# PX4FLOW1_3_1.net
KiCad netlist of a schematic drawn in EAGLE
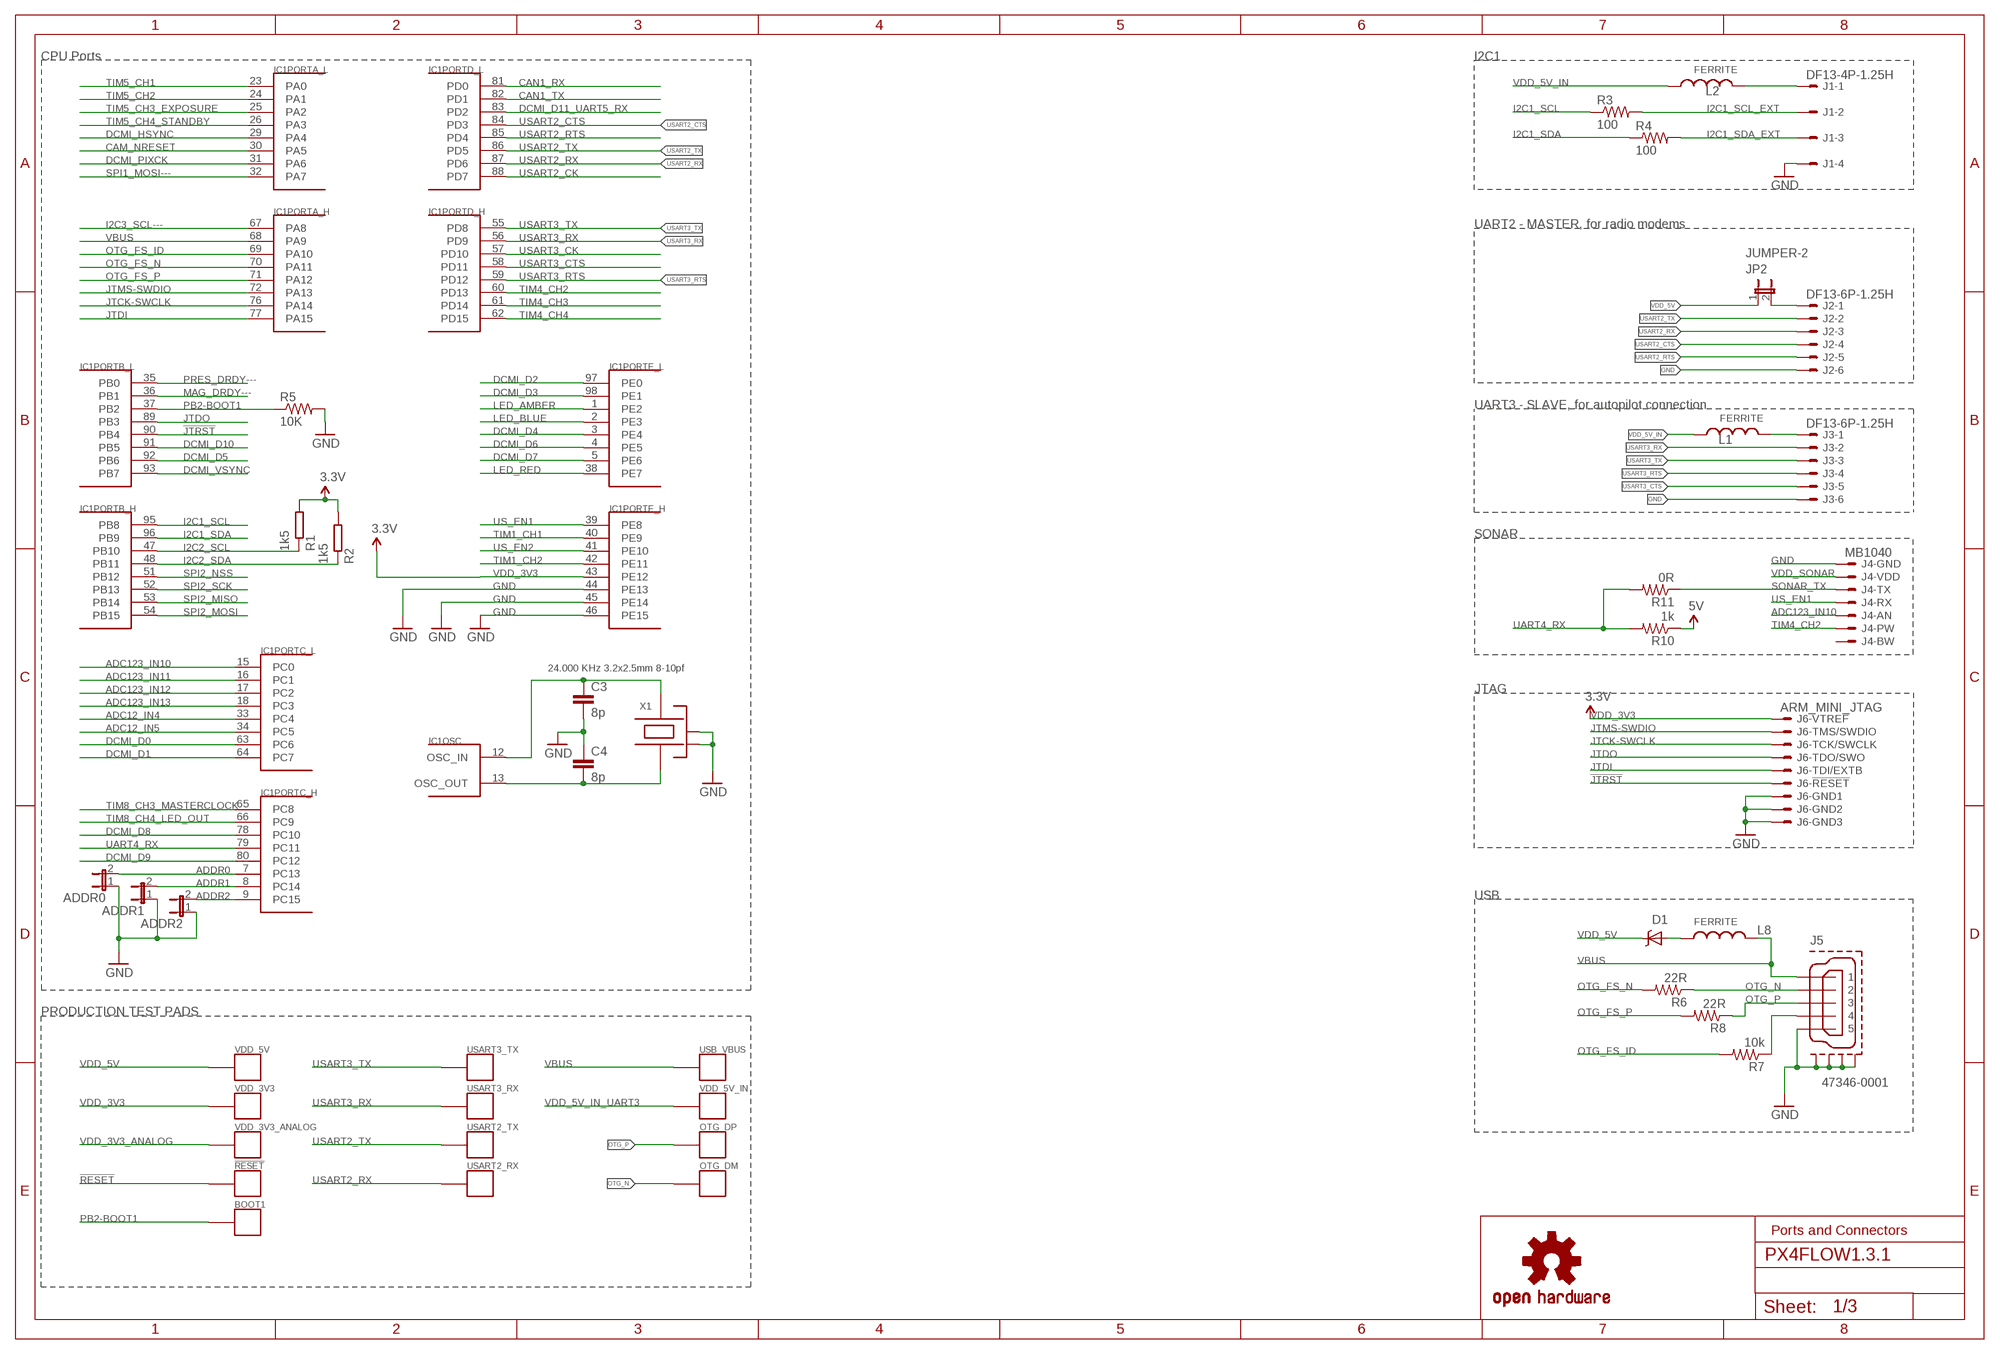
[diagram p0: schematic, sheet 1]
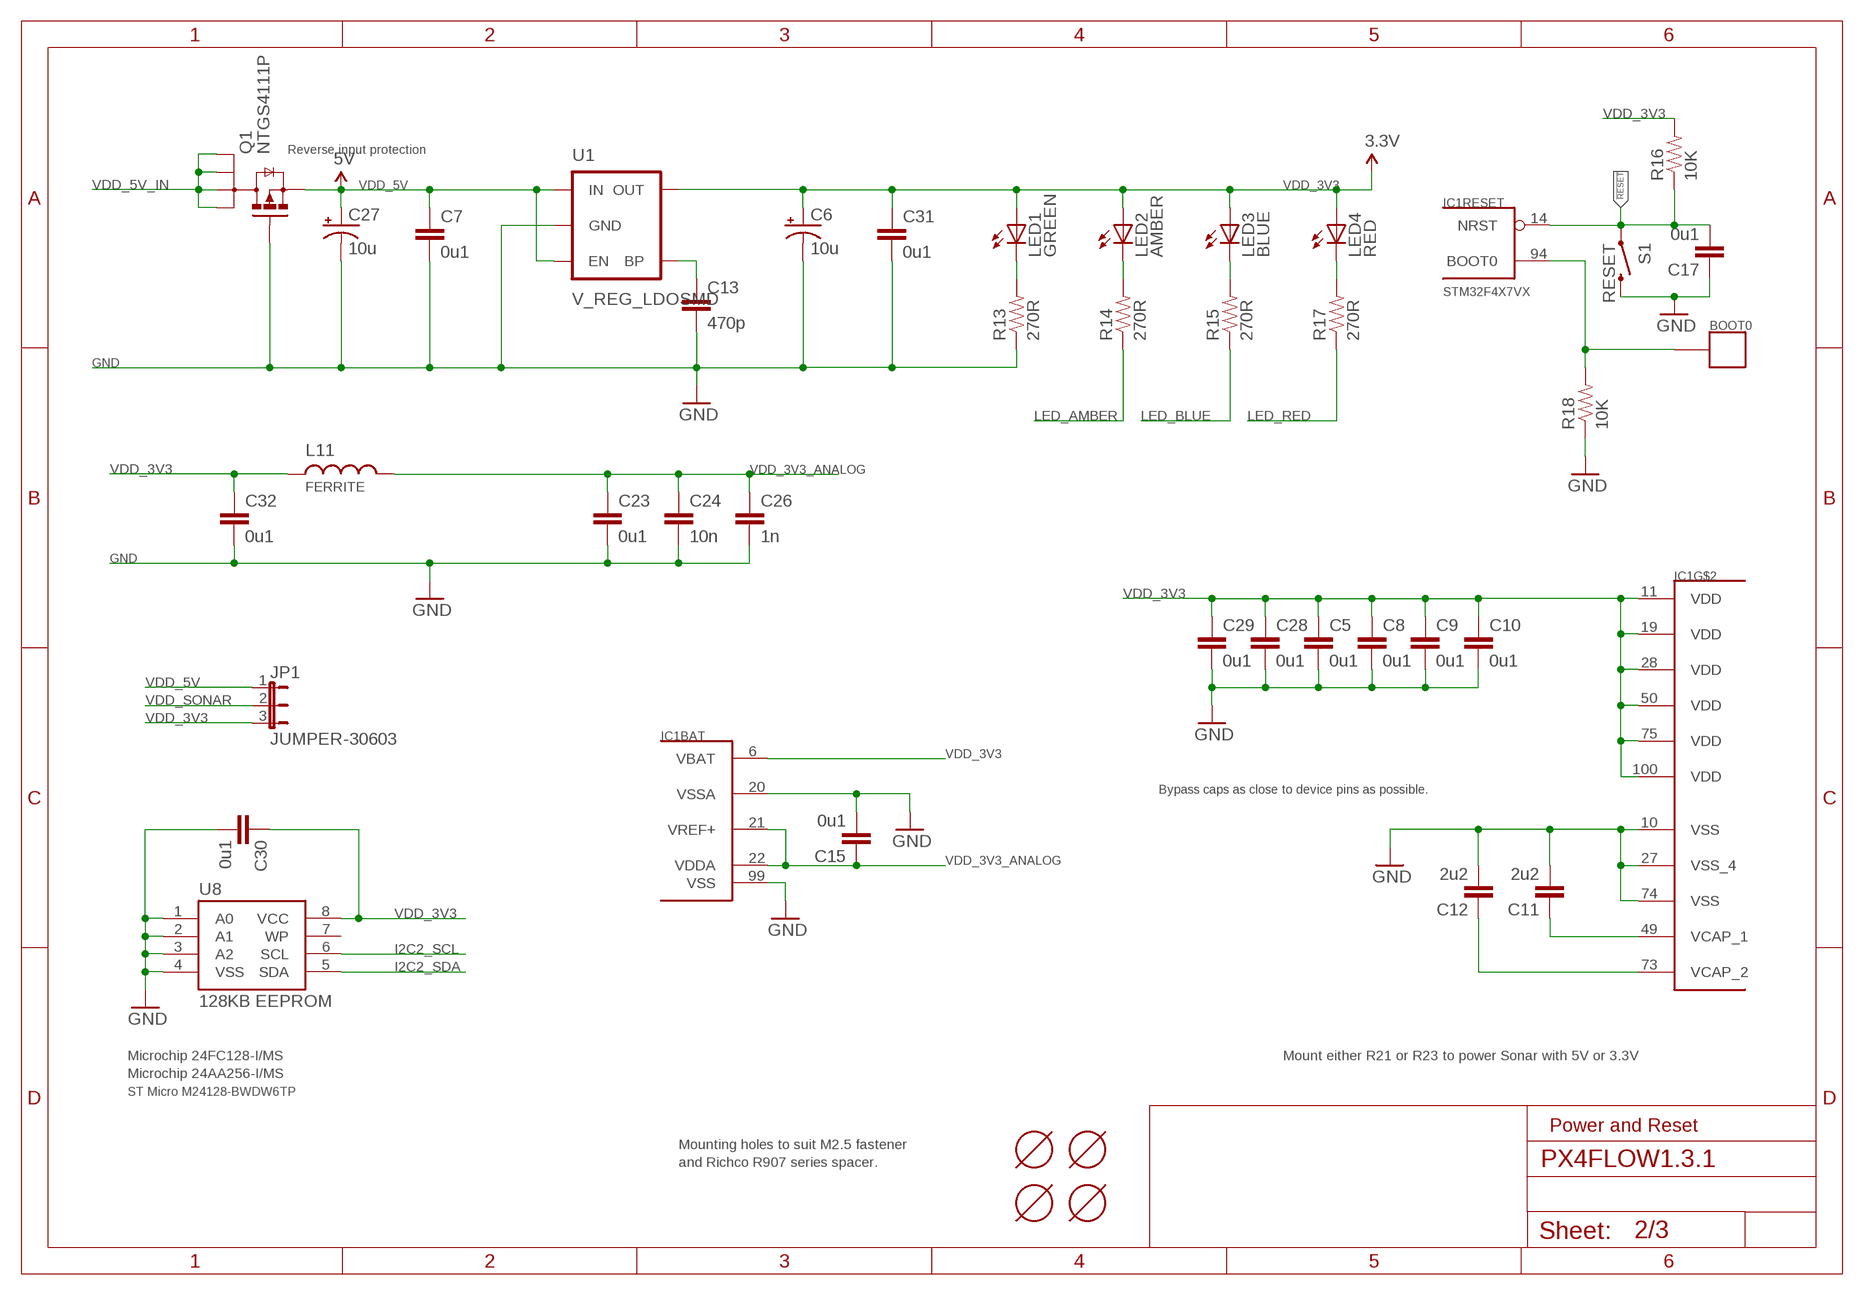
[diagram p1: schematic, sheet 2]
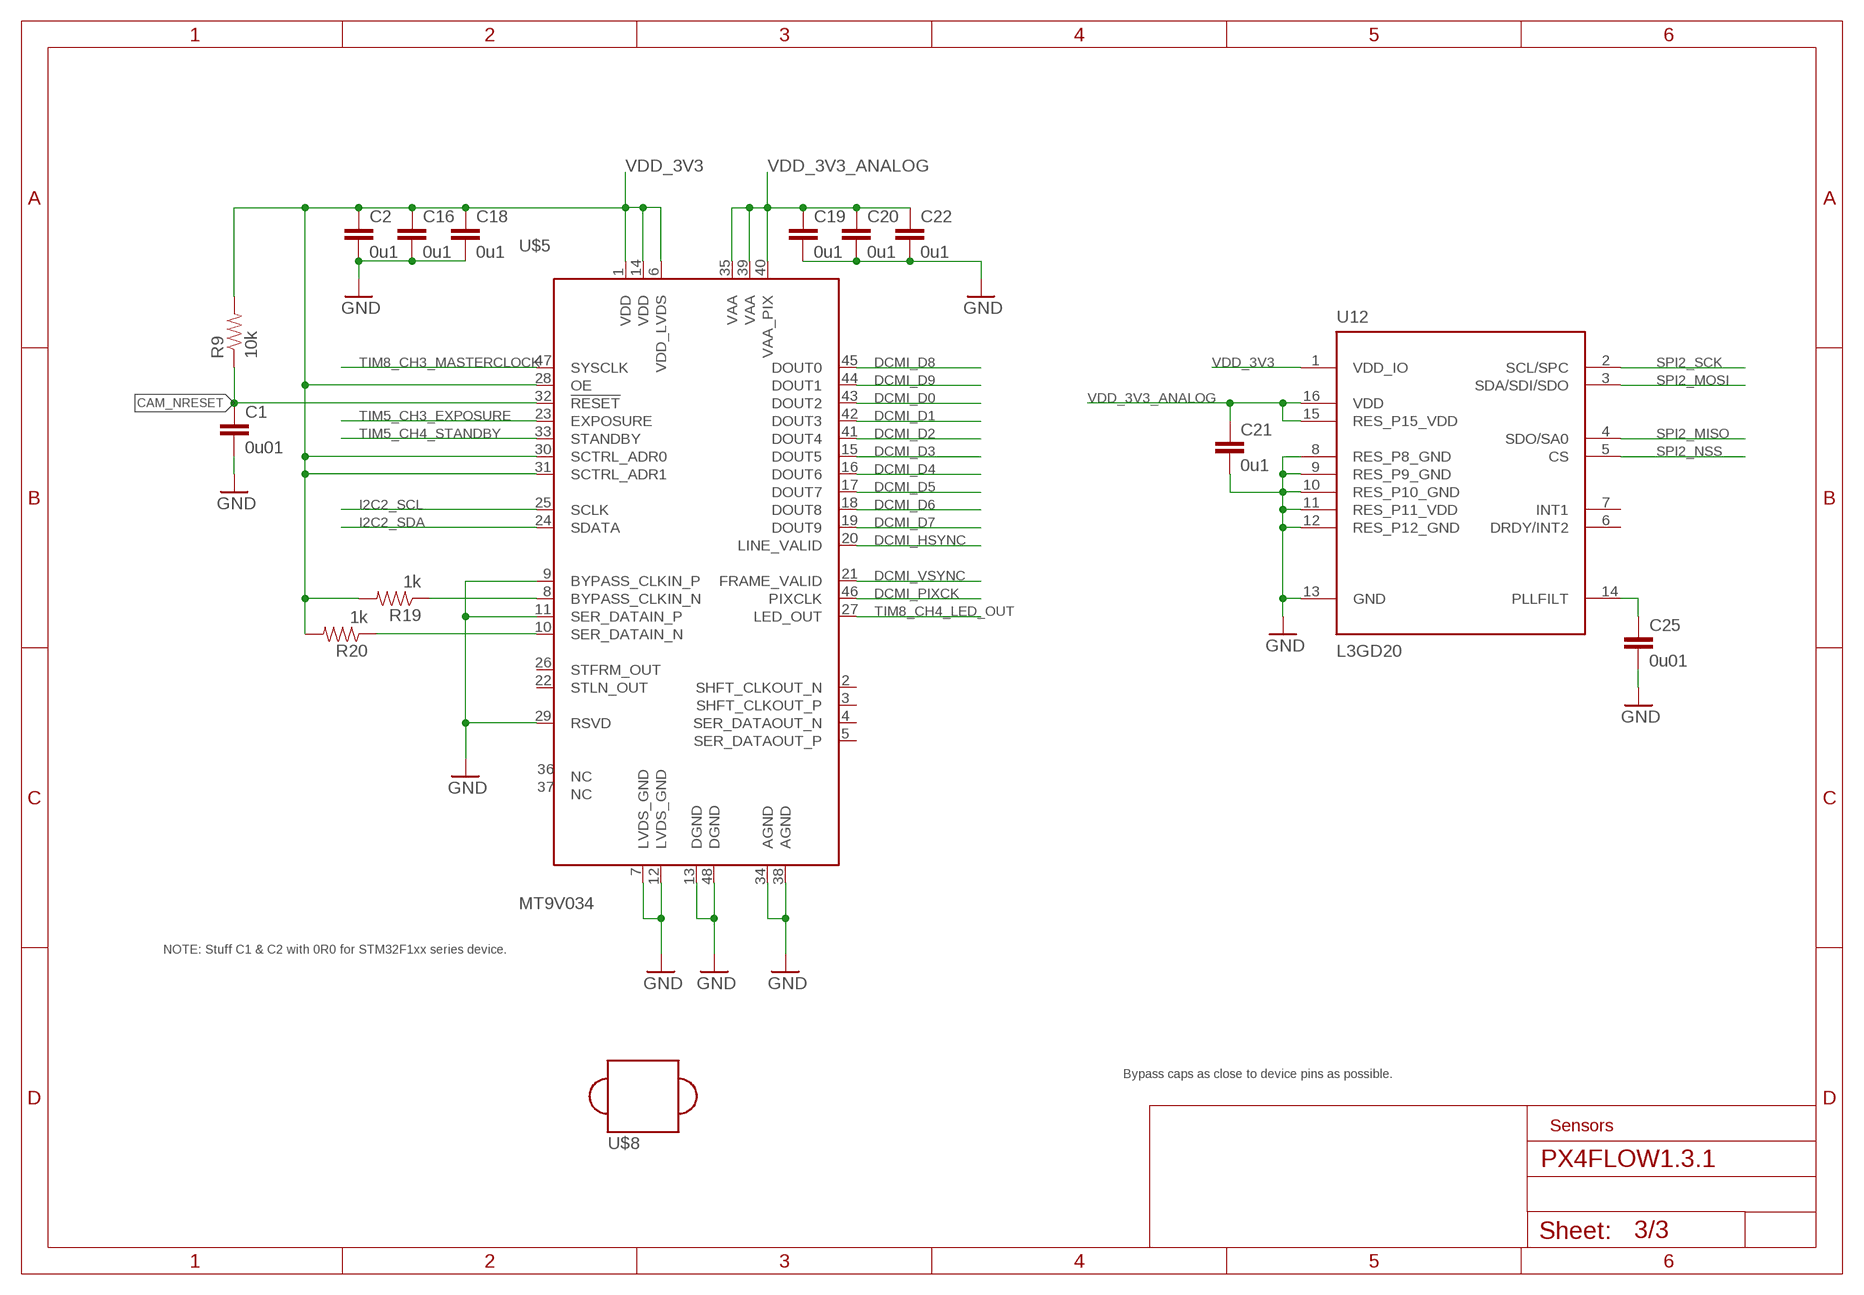
[diagram p2: schematic, sheet 3]

(export (version "E")
  (design (tool "Eeschema 10.0.6"))
  (components
    (comp (ref "BOOT0")
      (value "PAD.05")
      (footprint "eagle-import:PAD.05X.05")
      (libsource (lib "eagle-import") (part "PAD.05"))
    )
    (comp (ref "C5")
      (value "0u1")
      (footprint "eagle-import:0402-CAP")
      (fields (field (name "PARTNO") "CC0402ZRY5V7BB104"))
      (libsource (lib "eagle-import") (part "CAP0402-CAP"))
    )
    (comp (ref "C6")
      (value "10u")
      (footprint "eagle-import:EIA3216")
      (fields (field (name "PARTNO") "F931A106MAA"))
      (libsource (lib "eagle-import") (part "CAP_POL1206"))
    )
    (comp (ref "C7")
      (value "0u1")
      (footprint "eagle-import:0402-CAP")
      (fields (field (name "PARTNO") "CC0402ZRY5V7BB104"))
      (libsource (lib "eagle-import") (part "CAP0402-CAP"))
    )
    (comp (ref "C8")
      (value "0u1")
      (footprint "eagle-import:0402-CAP")
      (fields (field (name "PARTNO") "CC0402ZRY5V7BB104"))
      (libsource (lib "eagle-import") (part "CAP0402-CAP"))
    )
    (comp (ref "C9")
      (value "0u1")
      (footprint "eagle-import:0402-CAP")
      (fields (field (name "PARTNO") "CC0402ZRY5V7BB104"))
      (libsource (lib "eagle-import") (part "CAP0402-CAP"))
    )
    (comp (ref "C10")
      (value "0u1")
      (footprint "eagle-import:0402-CAP")
      (fields (field (name "PARTNO") "CC0402ZRY5V7BB104"))
      (libsource (lib "eagle-import") (part "CAP0402-CAP"))
    )
    (comp (ref "C11")
      (value "2u2")
      (footprint "eagle-import:0402-CAP")
      (fields (field (name "PARTNO") "C1608Y5V1C225Z"))
      (libsource (lib "eagle-import") (part "CAP0402-CAP"))
    )
    (comp (ref "C12")
      (value "2u2")
      (footprint "eagle-import:0402-CAP")
      (fields (field (name "PARTNO") "C1608Y5V1C225Z"))
      (libsource (lib "eagle-import") (part "CAP0402-CAP"))
    )
    (comp (ref "C13")
      (value "470p")
      (footprint "eagle-import:0402-CAP")
      (fields (field (name "PARTNO") "CC0402KRX7R9BB471"))
      (libsource (lib "eagle-import") (part "CAP0402-CAP"))
    )
    (comp (ref "C15")
      (value "0u1")
      (footprint "eagle-import:0402-CAP")
      (fields (field (name "PARTNO") "CC0402ZRY5V7BB104"))
      (libsource (lib "eagle-import") (part "CAP0402-CAP"))
    )
    (comp (ref "C17")
      (value "0u1")
      (footprint "eagle-import:0402-CAP")
      (fields (field (name "PARTNO") "CC0402ZRY5V7BB104"))
      (libsource (lib "eagle-import") (part "CAP0402-CAP"))
    )
    (comp (ref "C23")
      (value "0u1")
      (footprint "eagle-import:0402-CAP")
      (fields (field (name "PARTNO") "CC0402ZRY5V7BB104"))
      (libsource (lib "eagle-import") (part "CAP0402-CAP"))
    )
    (comp (ref "C24")
      (value "10n")
      (footprint "eagle-import:0402-CAP")
      (fields (field (name "PARTNO") "CC0402ZRY5V7BB104"))
      (libsource (lib "eagle-import") (part "CAP0402-CAP"))
    )
    (comp (ref "C26")
      (value "1n")
      (footprint "eagle-import:0402-CAP")
      (fields (field (name "PARTNO") "CC0402ZRY5V7BB104"))
      (libsource (lib "eagle-import") (part "CAP0402-CAP"))
    )
    (comp (ref "C27")
      (value "10u")
      (footprint "eagle-import:EIA3216")
      (fields (field (name "PARTNO") "F931A106MAA"))
      (libsource (lib "eagle-import") (part "CAP_POL1206"))
    )
    (comp (ref "C28")
      (value "0u1")
      (footprint "eagle-import:0402-CAP")
      (fields (field (name "PARTNO") "CC0402ZRY5V7BB104"))
      (libsource (lib "eagle-import") (part "CAP0402-CAP"))
    )
    (comp (ref "C29")
      (value "0u1")
      (footprint "eagle-import:0402-CAP")
      (fields (field (name "PARTNO") "CC0402ZRY5V7BB104"))
      (libsource (lib "eagle-import") (part "CAP0402-CAP"))
    )
    (comp (ref "C30")
      (value "0u1")
      (footprint "eagle-import:0402-CAP")
      (fields (field (name "PARTNO") "CC0402ZRY5V7BB104"))
      (libsource (lib "eagle-import") (part "CAP0402-CAP"))
    )
    (comp (ref "C31")
      (value "0u1")
      (footprint "eagle-import:0402-CAP")
      (fields (field (name "PARTNO") "CC0402ZRY5V7BB104"))
      (libsource (lib "eagle-import") (part "CAP0402-CAP"))
    )
    (comp (ref "C32")
      (value "0u1")
      (footprint "eagle-import:0402-CAP")
      (fields (field (name "PARTNO") "CC0402ZRY5V7BB104"))
      (libsource (lib "eagle-import") (part "CAP0402-CAP"))
    )
    (comp (ref "IC1")
      (value "STM32F4X7VX")
      (footprint "eagle-import:TQFP100")
      (fields (field (name "PARTNO") "STM32F407VGT6"))
      (libsource (lib "eagle-import") (part "STM32F4X7VX"))
    )
    (comp (ref "JP1")
      (value "JUMPER-30603")
      (footprint "eagle-import:SJ_3_0603_PASTE1&2")
      (fields (field (name "PARTNO") "RMCF0402ZT0R00"))
      (libsource (lib "eagle-import") (part "JUMPER-30603"))
    )
    (comp (ref "L11")
      (value "FERRITE")
      (footprint "eagle-import:0402-IND")
      (fields (field (name "PARTNO") "BKP1005HS121-T"))
      (libsource (lib "eagle-import") (part "INDUCTOR0402"))
    )
    (comp (ref "LED1")
      (value "GREEN")
      (footprint "eagle-import:LED-0603")
      (fields (field (name "PARTNO") "LNJ337W83RA"))
      (libsource (lib "eagle-import") (part "LED0603"))
    )
    (comp (ref "LED2")
      (value "AMBER")
      (footprint "eagle-import:LED-0603")
      (fields (field (name "PARTNO") "LNJ437W84RA"))
      (libsource (lib "eagle-import") (part "LED0603"))
    )
    (comp (ref "LED3")
      (value "BLUE")
      (footprint "eagle-import:LED-0603")
      (fields (field (name "PARTNO") "LNJ937W8CRA"))
      (libsource (lib "eagle-import") (part "LED0603"))
    )
    (comp (ref "LED4")
      (value "RED")
      (footprint "eagle-import:LED-0603")
      (fields (field (name "PARTNO") "LNJ237W82RA"))
      (libsource (lib "eagle-import") (part "LED0603"))
    )
    (comp (ref "Q1")
      (value "NTGS4111P")
      (footprint "eagle-import:TSOP-6")
      (libsource (lib "eagle-import") (part "NTGS4111P"))
    )
    (comp (ref "R13")
      (value "270R")
      (footprint "eagle-import:0402-RES")
      (fields (field (name "PARTNO") "MCR01MZPJ271"))
      (libsource (lib "eagle-import") (part "RESISTOR0402-RES"))
    )
    (comp (ref "R14")
      (value "270R")
      (footprint "eagle-import:0402-RES")
      (fields (field (name "PARTNO") "MCR01MZPJ271"))
      (libsource (lib "eagle-import") (part "RESISTOR0402-RES"))
    )
    (comp (ref "R15")
      (value "270R")
      (footprint "eagle-import:0402-RES")
      (fields (field (name "PARTNO") "MCR01MZPJ820"))
      (libsource (lib "eagle-import") (part "RESISTOR0402-RES"))
    )
    (comp (ref "R16")
      (value "10K")
      (footprint "eagle-import:0402-RES")
      (fields (field (name "PARTNO") "RMCF0402FT10K0"))
      (libsource (lib "eagle-import") (part "RESISTOR0402-RES"))
    )
    (comp (ref "R17")
      (value "270R")
      (footprint "eagle-import:0402-RES")
      (fields (field (name "PARTNO") "MCR01MZPJ820"))
      (libsource (lib "eagle-import") (part "RESISTOR0402-RES"))
    )
    (comp (ref "R18")
      (value "10K")
      (footprint "eagle-import:0402-RES")
      (fields (field (name "PARTNO") "RMCF0402FT10K0"))
      (libsource (lib "eagle-import") (part "RESISTOR0402-RES"))
    )
    (comp (ref "S1")
      (value "RESET")
      (footprint "eagle-import:EVQP7J01K")
      (fields (field (name "PARTNO") "EVQP7J01K"))
      (libsource (lib "eagle-import") (part "SWITCH-MOMENTARY-2"))
    )
    (comp (ref "U$1")
      (value "MOUNT-HOLE3.1MM")
      (footprint "eagle-import:MOUNT-HOLE3.1")
      (libsource (lib "eagle-import") (part "MOUNT-HOLE3.1MM"))
    )
    (comp (ref "U$2")
      (value "MOUNT-HOLE3.1MM")
      (footprint "eagle-import:MOUNT-HOLE3.1")
      (libsource (lib "eagle-import") (part "MOUNT-HOLE3.1MM"))
    )
    (comp (ref "U$3")
      (value "MOUNT-HOLE3.1MM")
      (footprint "eagle-import:MOUNT-HOLE3.1")
      (libsource (lib "eagle-import") (part "MOUNT-HOLE3.1MM"))
    )
    (comp (ref "U$4")
      (value "MOUNT-HOLE3.1MM")
      (footprint "eagle-import:MOUNT-HOLE3.1")
      (libsource (lib "eagle-import") (part "MOUNT-HOLE3.1MM"))
    )
    (comp (ref "U1")
      (value "V_REG_LDOSMD")
      (footprint "eagle-import:SOT23-5")
      (fields (field (name "PARTNO") "MIC5207-3.3YM5"))
      (libsource (lib "eagle-import") (part "V_REG_LDOSMD"))
    )
    (comp (ref "U8")
      (value "128KB EEPROM")
      (footprint "eagle-import:MSOP-8")
      (fields (field (name "PARTNO") "24FC128-I/MS"))
      (libsource (lib "eagle-import") (part "EEPROM-I2CMSOP"))
    )
    (comp (ref "!RESET")
      (value "PAD.04")
      (footprint "eagle-import:PAD.04X.04")
      (libsource (lib "eagle-import") (part "PAD.04"))
    )
    (comp (ref "ADDR0")
      (value "JUMPER-2")
      (footprint "eagle-import:SJ_2")
      (libsource (lib "eagle-import") (part "JUMPER-2"))
    )
    (comp (ref "ADDR1")
      (value "JUMPER-2")
      (footprint "eagle-import:SJ_2")
      (libsource (lib "eagle-import") (part "JUMPER-2"))
    )
    (comp (ref "ADDR2")
      (value "JUMPER-2")
      (footprint "eagle-import:SJ_2")
      (libsource (lib "eagle-import") (part "JUMPER-2"))
    )
    (comp (ref "BOOT1")
      (value "PAD.04")
      (footprint "eagle-import:PAD.04X.04")
      (libsource (lib "eagle-import") (part "PAD.04"))
    )
    (comp (ref "C3")
      (value "8p")
      (footprint "eagle-import:0402-CAP")
      (libsource (lib "eagle-import") (part "CAPACITOR-0402"))
    )
    (comp (ref "C4")
      (value "8p")
      (footprint "eagle-import:0402-CAP")
      (libsource (lib "eagle-import") (part "CAPACITOR-0402"))
    )
    (comp (ref "D1")
      (value "MSS1P4-M3")
      (footprint "eagle-import:MICROSMP")
      (fields (field (name "PARTNO") "MSS1P4-M3/89A"))
      (libsource (lib "eagle-import") (part "DIODE-SCHOTTKY_MSMP"))
    )
    (comp (ref "J1")
      (value "DF13-4P-1.25H")
      (footprint "eagle-import:DF13A-4P-1.25H")
      (fields (field (name "PARTNO") "DF13A-4P-1.25H(20)"))
      (libsource (lib "eagle-import") (part "DF13-4P-1.25?H"))
    )
    (comp (ref "J2")
      (value "DF13-6P-1.25H")
      (footprint "eagle-import:DF13A-6P-1.25H")
      (fields (field (name "PARTNO") "DF13A-6P-1.25H(20)"))
      (libsource (lib "eagle-import") (part "DF13-6P-1.25?H"))
    )
    (comp (ref "J3")
      (value "DF13-6P-1.25H")
      (footprint "eagle-import:DF13A-6P-1.25H")
      (fields (field (name "PARTNO") "DF13A-6P-1.25H(20)"))
      (libsource (lib "eagle-import") (part "DF13-6P-1.25?H"))
    )
    (comp (ref "J4")
      (value "MB1040")
      (footprint "eagle-import:MAXSONAR")
      (fields (field (name "BOM") "EXCLUDE") (field (name "PARTNO") "*"))
      (libsource (lib "eagle-import") (part "MAXSONAR"))
    )
    (comp (ref "J5")
      (value "47346-0001")
      (footprint "eagle-import:MOLEX-47346-0001")
      (libsource (lib "eagle-import") (part "MOLEX-47346-0001"))
    )
    (comp (ref "J6")
      (value "ARM_MINI_JTAG")
      (footprint "eagle-import:FTSH-105-01-XXX-DV-K")
      (fields (field (name "PARTNO") "M50-3900542"))
      (libsource (lib "eagle-import") (part "ARM_MINI_JTAG-SMT"))
    )
    (comp (ref "JP2")
      (value "JUMPER-2")
      (footprint "eagle-import:SJ_2")
      (libsource (lib "eagle-import") (part "JUMPER-2"))
    )
    (comp (ref "L1")
      (value "FERRITE")
      (footprint "eagle-import:0402-IND")
      (fields (field (name "PARTNO") "BKP1005HS121-T"))
      (libsource (lib "eagle-import") (part "INDUCTOR0402"))
    )
    (comp (ref "L2")
      (value "FERRITE")
      (footprint "eagle-import:0402-IND")
      (fields (field (name "PARTNO") "BKP1005HS121-T"))
      (libsource (lib "eagle-import") (part "INDUCTOR0402"))
    )
    (comp (ref "L8")
      (value "FERRITE")
      (footprint "eagle-import:0402-IND")
      (fields (field (name "PARTNO") "BKP1005HS121-T"))
      (libsource (lib "eagle-import") (part "INDUCTOR0402"))
    )
    (comp (ref "OTG_DM")
      (value "PAD.04")
      (footprint "eagle-import:PAD.04X.04")
      (libsource (lib "eagle-import") (part "PAD.04"))
    )
    (comp (ref "OTG_DP")
      (value "PAD.04")
      (footprint "eagle-import:PAD.04X.04")
      (libsource (lib "eagle-import") (part "PAD.04"))
    )
    (comp (ref "R1")
      (value "1k5")
      (footprint "eagle-import:0402-RES")
      (libsource (lib "eagle-import") (part "RESISTOR-0402"))
    )
    (comp (ref "R2")
      (value "1k5")
      (footprint "eagle-import:0402-RES")
      (libsource (lib "eagle-import") (part "RESISTOR-0402"))
    )
    (comp (ref "R3")
      (value "100")
      (footprint "eagle-import:0402-RES")
      (fields (field (name "PARTNO") "RMCF0402JT100R"))
      (libsource (lib "eagle-import") (part "RESISTOR0402-RES"))
    )
    (comp (ref "R4")
      (value "100")
      (footprint "eagle-import:0402-RES")
      (fields (field (name "PARTNO") "RMCF0402JT100R"))
      (libsource (lib "eagle-import") (part "RESISTOR0402-RES"))
    )
    (comp (ref "R5")
      (value "10K")
      (footprint "eagle-import:0402-RES")
      (fields (field (name "PARTNO") "RMCF0402FT10K0"))
      (libsource (lib "eagle-import") (part "RESISTOR0402-RES"))
    )
    (comp (ref "R6")
      (value "22R")
      (footprint "eagle-import:0402-RES")
      (fields (field (name "PARTNO") "RMCF0402JT22R0"))
      (libsource (lib "eagle-import") (part "RESISTOR0402-RES"))
    )
    (comp (ref "R7")
      (value "10k")
      (footprint "eagle-import:0402-RES")
      (fields (field (name "PARTNO") "MFR-25FBF-10K0"))
      (libsource (lib "eagle-import") (part "RESISTOR0402-RES"))
    )
    (comp (ref "R8")
      (value "22R")
      (footprint "eagle-import:0402-RES")
      (fields (field (name "PARTNO") "RMCF0402JT22R0"))
      (libsource (lib "eagle-import") (part "RESISTOR0402-RES"))
    )
    (comp (ref "R10")
      (value "1k")
      (footprint "eagle-import:0402-RES")
      (fields (field (name "PARTNO") "RMCF0402JT1K00"))
      (libsource (lib "eagle-import") (part "RESISTOR0402-RES"))
    )
    (comp (ref "R11")
      (value "0R")
      (footprint "eagle-import:0402-RES")
      (fields (field (name "PARTNO") "RMCF0402JT1K00"))
      (libsource (lib "eagle-import") (part "RESISTOR0402-RES"))
    )
    (comp (ref "U$10")
      (value "OSHW-LOGOS")
      (footprint "eagle-import:OSHW-LOGO-S")
      (libsource (lib "eagle-import") (part "OSHW-LOGOS"))
    )
    (comp (ref "USART2_RX")
      (value "PAD.04")
      (footprint "eagle-import:PAD.04X.04")
      (libsource (lib "eagle-import") (part "PAD.04"))
    )
    (comp (ref "USART2_TX")
      (value "PAD.04")
      (footprint "eagle-import:PAD.04X.04")
      (libsource (lib "eagle-import") (part "PAD.04"))
    )
    (comp (ref "USART3_RX")
      (value "PAD.04")
      (footprint "eagle-import:PAD.04X.04")
      (libsource (lib "eagle-import") (part "PAD.04"))
    )
    (comp (ref "USART3_TX")
      (value "PAD.04")
      (footprint "eagle-import:PAD.04X.04")
      (libsource (lib "eagle-import") (part "PAD.04"))
    )
    (comp (ref "USB_VBUS")
      (value "PAD.04")
      (footprint "eagle-import:PAD.04X.04")
      (libsource (lib "eagle-import") (part "PAD.04"))
    )
    (comp (ref "VDD_3V3")
      (value "PAD.04")
      (footprint "eagle-import:PAD.04X.04")
      (libsource (lib "eagle-import") (part "PAD.04"))
    )
    (comp (ref "VDD_3V3_ANALOG")
      (value "PAD.04")
      (footprint "eagle-import:PAD.04X.04")
      (libsource (lib "eagle-import") (part "PAD.04"))
    )
    (comp (ref "VDD_5V")
      (value "PAD.04")
      (footprint "eagle-import:PAD.04X.04")
      (libsource (lib "eagle-import") (part "PAD.04"))
    )
    (comp (ref "VDD_5V_IN")
      (value "PAD.04")
      (footprint "eagle-import:PAD.04X.04")
      (libsource (lib "eagle-import") (part "PAD.04"))
    )
    (comp (ref "X1")
      (value "24.000 KHz 3.2x2.5mm 8-10pf")
      (footprint "eagle-import:OSCILLATOR-3.2X2.5")
      (fields (field (name "PARTNO") "NX3225SA-24.000000MHZ"))
      (libsource (lib "eagle-import") (part "OSCILLATOR-3.2X2.5"))
    )
    (comp (ref "C1")
      (value "0u01")
      (footprint "eagle-import:0402-CAP")
      (fields (field (name "PARTNO") "CC0402KRX7R7BB103"))
      (libsource (lib "eagle-import") (part "CAP0402-CAP"))
    )
    (comp (ref "C2")
      (value "0u1")
      (footprint "eagle-import:0402-CAP")
      (fields (field (name "PARTNO") "CC0402ZRY5V7BB104"))
      (libsource (lib "eagle-import") (part "CAP0402-CAP"))
    )
    (comp (ref "C16")
      (value "0u1")
      (footprint "eagle-import:0402-CAP")
      (fields (field (name "PARTNO") "CC0402ZRY5V7BB104"))
      (libsource (lib "eagle-import") (part "CAP0402-CAP"))
    )
    (comp (ref "C18")
      (value "0u1")
      (footprint "eagle-import:0402-CAP")
      (fields (field (name "PARTNO") "CC0402ZRY5V7BB104"))
      (libsource (lib "eagle-import") (part "CAP0402-CAP"))
    )
    (comp (ref "C19")
      (value "0u1")
      (footprint "eagle-import:0402-CAP")
      (fields (field (name "PARTNO") "CC0402ZRY5V7BB104"))
      (libsource (lib "eagle-import") (part "CAP0402-CAP"))
    )
    (comp (ref "C20")
      (value "0u1")
      (footprint "eagle-import:0402-CAP")
      (fields (field (name "PARTNO") "CC0402ZRY5V7BB104"))
      (libsource (lib "eagle-import") (part "CAP0402-CAP"))
    )
    (comp (ref "C21")
      (value "0u1")
      (footprint "eagle-import:0402-CAP")
      (fields (field (name "PARTNO") "CC0402ZRY5V7BB104"))
      (libsource (lib "eagle-import") (part "CAP0402-CAP"))
    )
    (comp (ref "C22")
      (value "0u1")
      (footprint "eagle-import:0402-CAP")
      (fields (field (name "PARTNO") "CC0402ZRY5V7BB104"))
      (libsource (lib "eagle-import") (part "CAP0402-CAP"))
    )
    (comp (ref "C25")
      (value "0u01")
      (footprint "eagle-import:0402-CAP")
      (fields (field (name "PARTNO") "CC0402KRX7R7BB103"))
      (libsource (lib "eagle-import") (part "CAP0402-CAP"))
    )
    (comp (ref "R9")
      (value "10k")
      (footprint "eagle-import:0402-RES")
      (fields (field (name "PARTNO") "MCR01MZPJ271"))
      (libsource (lib "eagle-import") (part "RESISTOR0402-RES"))
    )
    (comp (ref "R19")
      (value "1k")
      (footprint "eagle-import:0402-RES")
      (fields (field (name "PARTNO") "RMCF0402JT1K00"))
      (libsource (lib "eagle-import") (part "RESISTOR0402-RES"))
    )
    (comp (ref "R20")
      (value "1k")
      (footprint "eagle-import:0402-RES")
      (fields (field (name "PARTNO") "RMCF0402JT1K00"))
      (libsource (lib "eagle-import") (part "RESISTOR0402-RES"))
    )
    (comp (ref "U$5")
      (value "MT9V034")
      (footprint "eagle-import:CLCC-48")
      (fields (field (name "PARTNO") "MT9V034C12STM"))
      (libsource (lib "eagle-import") (part "MT9V034"))
    )
    (comp (ref "U$8")
      (value "LENSMOUNT_M12")
      (footprint "eagle-import:LENSMOUNT_LARGE_M12")
      (libsource (lib "eagle-import") (part "LENSMOUNT_M12"))
    )
    (comp (ref "U12")
      (value "L3GD20")
      (footprint "eagle-import:L3G4200DH-MAN")
      (libsource (lib "eagle-import") (part "L3G4200DH-LL"))
    )
  )
  (nets
    (net (code "1") (name "ADC12_IN4") (class "Default")
      (node (ref "IC1") (pin "33") (pinfunction "PC4_33") (pintype "bidirectional"))
    )
    (net (code "2") (name "ADC12_IN5") (class "Default")
      (node (ref "IC1") (pin "34") (pinfunction "PC5_34") (pintype "bidirectional"))
    )
    (net (code "3") (name "ADC123_IN10") (class "Default")
      (node (ref "IC1") (pin "15") (pinfunction "PC0_15") (pintype "bidirectional"))
      (node (ref "J4") (pin "AN") (pinfunction "S_AN") (pintype "passive"))
    )
    (net (code "4") (name "ADC123_IN11") (class "Default")
      (node (ref "IC1") (pin "16") (pinfunction "PC1_16") (pintype "bidirectional"))
    )
    (net (code "5") (name "ADC123_IN12") (class "Default")
      (node (ref "IC1") (pin "17") (pinfunction "PC2_17") (pintype "bidirectional"))
    )
    (net (code "6") (name "ADC123_IN13") (class "Default")
      (node (ref "IC1") (pin "18") (pinfunction "PC3_18") (pintype "bidirectional"))
    )
    (net (code "7") (name "ADDR0") (class "Default")
      (node (ref "ADDR0") (pin "2") (pinfunction "2_2") (pintype "passive"))
      (node (ref "IC1") (pin "7") (pinfunction "PC13_7") (pintype "bidirectional"))
    )
    (net (code "8") (name "ADDR1") (class "Default")
      (node (ref "ADDR1") (pin "2") (pinfunction "2_2") (pintype "passive"))
      (node (ref "IC1") (pin "8") (pinfunction "PC14_8") (pintype "bidirectional"))
    )
    (net (code "9") (name "ADDR2") (class "Default")
      (node (ref "ADDR2") (pin "2") (pinfunction "2_2") (pintype "passive"))
      (node (ref "IC1") (pin "9") (pinfunction "PC15_9") (pintype "bidirectional"))
    )
    (net (code "10") (name "CAM_NRESET") (class "Default")
      (node (ref "C1") (pin "1") (pinfunction "1_1") (pintype "passive"))
      (node (ref "IC1") (pin "30") (pinfunction "PA5_30") (pintype "bidirectional"))
      (node (ref "R9") (pin "1") (pinfunction "1_1") (pintype "passive"))
      (node (ref "U$5") (pin "32") (pinfunction "~{RESET}_32") (pintype "input"))
    )
    (net (code "11") (name "CAN1_RX") (class "Default")
      (node (ref "IC1") (pin "81") (pinfunction "PD0_81") (pintype "bidirectional"))
    )
    (net (code "12") (name "CAN1_TX") (class "Default")
      (node (ref "IC1") (pin "82") (pinfunction "PD1_82") (pintype "bidirectional"))
    )
    (net (code "13") (name "DCMI_D0") (class "Default")
      (node (ref "IC1") (pin "63") (pinfunction "PC6_63") (pintype "bidirectional"))
      (node (ref "U$5") (pin "43") (pinfunction "DOUT2_43") (pintype "output"))
    )
    (net (code "14") (name "DCMI_D1") (class "Default")
      (node (ref "IC1") (pin "64") (pinfunction "PC7_64") (pintype "bidirectional"))
      (node (ref "U$5") (pin "42") (pinfunction "DOUT3_42") (pintype "output"))
    )
    (net (code "15") (name "DCMI_D2") (class "Default")
      (node (ref "IC1") (pin "97") (pinfunction "PE0_97") (pintype "bidirectional"))
      (node (ref "U$5") (pin "41") (pinfunction "DOUT4_41") (pintype "output"))
    )
    (net (code "16") (name "DCMI_D3") (class "Default")
      (node (ref "IC1") (pin "98") (pinfunction "PE1_98") (pintype "bidirectional"))
      (node (ref "U$5") (pin "15") (pinfunction "DOUT5_15") (pintype "output"))
    )
    (net (code "17") (name "DCMI_D4") (class "Default")
      (node (ref "IC1") (pin "3") (pinfunction "PE4_3") (pintype "bidirectional"))
      (node (ref "U$5") (pin "16") (pinfunction "DOUT6_16") (pintype "output"))
    )
    (net (code "18") (name "DCMI_D5") (class "Default")
      (node (ref "IC1") (pin "92") (pinfunction "PB6_92") (pintype "bidirectional"))
      (node (ref "U$5") (pin "17") (pinfunction "DOUT7_17") (pintype "output"))
    )
    (net (code "19") (name "DCMI_D6") (class "Default")
      (node (ref "IC1") (pin "4") (pinfunction "PE5_4") (pintype "bidirectional"))
      (node (ref "U$5") (pin "18") (pinfunction "DOUT8_18") (pintype "output"))
    )
    (net (code "20") (name "DCMI_D7") (class "Default")
      (node (ref "IC1") (pin "5") (pinfunction "PE6_5") (pintype "bidirectional"))
      (node (ref "U$5") (pin "19") (pinfunction "DOUT9_19") (pintype "output"))
    )
    (net (code "21") (name "DCMI_D8") (class "Default")
      (node (ref "IC1") (pin "78") (pinfunction "PC10_78") (pintype "bidirectional"))
      (node (ref "U$5") (pin "45") (pinfunction "DOUT0_45") (pintype "output"))
    )
    (net (code "22") (name "DCMI_D9") (class "Default")
      (node (ref "IC1") (pin "80") (pinfunction "PC12_80") (pintype "bidirectional"))
      (node (ref "U$5") (pin "44") (pinfunction "DOUT1_44") (pintype "output"))
    )
    (net (code "23") (name "DCMI_D10") (class "Default")
      (node (ref "IC1") (pin "91") (pinfunction "PB5_91") (pintype "bidirectional"))
    )
    (net (code "24") (name "DCMI_D11_UART5_RX") (class "Default")
      (node (ref "IC1") (pin "83") (pinfunction "PD2_83") (pintype "bidirectional"))
    )
    (net (code "25") (name "DCMI_HSYNC") (class "Default")
      (node (ref "IC1") (pin "29") (pinfunction "PA4_29") (pintype "bidirectional"))
      (node (ref "U$5") (pin "20") (pinfunction "LINE_VALID_20") (pintype "output"))
    )
    (net (code "26") (name "DCMI_PIXCK") (class "Default")
      (node (ref "IC1") (pin "31") (pinfunction "PA6_31") (pintype "bidirectional"))
      (node (ref "U$5") (pin "46") (pinfunction "PIXCLK_46") (pintype "output"))
    )
    (net (code "27") (name "DCMI_VSYNC") (class "Default")
      (node (ref "IC1") (pin "93") (pinfunction "PB7_93") (pintype "bidirectional"))
      (node (ref "U$5") (pin "21") (pinfunction "FRAME_VALID_21") (pintype "output"))
    )
    (net (code "28") (name "GND") (class "Default")
      (node (ref "ADDR0") (pin "1") (pinfunction "1_1") (pintype "passive"))
      (node (ref "ADDR1") (pin "1") (pinfunction "1_1") (pintype "passive"))
      (node (ref "ADDR2") (pin "1") (pinfunction "1_1") (pintype "passive"))
      (node (ref "C1") (pin "2") (pinfunction "2_2") (pintype "passive"))
      (node (ref "C10") (pin "2") (pinfunction "2_2") (pintype "passive"))
      (node (ref "C11") (pin "2") (pinfunction "2_2") (pintype "passive"))
      (node (ref "C12") (pin "2") (pinfunction "2_2") (pintype "passive"))
      (node (ref "C13") (pin "2") (pinfunction "2_2") (pintype "passive"))
      (node (ref "C15") (pin "2") (pinfunction "2_2") (pintype "passive"))
      (node (ref "C16") (pin "2") (pinfunction "2_2") (pintype "passive"))
      (node (ref "C17") (pin "1") (pinfunction "1_1") (pintype "passive"))
      (node (ref "C18") (pin "2") (pinfunction "2_2") (pintype "passive"))
      (node (ref "C19") (pin "2") (pinfunction "2_2") (pintype "passive"))
      (node (ref "C2") (pin "2") (pinfunction "2_2") (pintype "passive"))
      (node (ref "C20") (pin "2") (pinfunction "2_2") (pintype "passive"))
      (node (ref "C21") (pin "2") (pinfunction "2_2") (pintype "passive"))
      (node (ref "C22") (pin "2") (pinfunction "2_2") (pintype "passive"))
      (node (ref "C23") (pin "2") (pinfunction "2_2") (pintype "passive"))
      (node (ref "C24") (pin "2") (pinfunction "2_2") (pintype "passive"))
      (node (ref "C25") (pin "2") (pinfunction "2_2") (pintype "passive"))
      (node (ref "C26") (pin "2") (pinfunction "2_2") (pintype "passive"))
      (node (ref "C27") (pin "C") (pinfunction "-_C") (pintype "passive"))
      (node (ref "C28") (pin "2") (pinfunction "2_2") (pintype "passive"))
      (node (ref "C29") (pin "2") (pinfunction "2_2") (pintype "passive"))
      (node (ref "C3") (pin "P$2") (pinfunction "2_P$2") (pintype "passive"))
      (node (ref "C30") (pin "2") (pinfunction "2_2") (pintype "passive"))
      (node (ref "C31") (pin "2") (pinfunction "2_2") (pintype "passive"))
      (node (ref "C32") (pin "2") (pinfunction "2_2") (pintype "passive"))
      (node (ref "C4") (pin "P$1") (pinfunction "1_P$1") (pintype "passive"))
      (node (ref "C5") (pin "2") (pinfunction "2_2") (pintype "passive"))
      (node (ref "C6") (pin "C") (pinfunction "-_C") (pintype "passive"))
      (node (ref "C7") (pin "2") (pinfunction "2_2") (pintype "passive"))
      (node (ref "C8") (pin "2") (pinfunction "2_2") (pintype "passive"))
      (node (ref "C9") (pin "2") (pinfunction "2_2") (pintype "passive"))
      (node (ref "IC1") (pin "10") (pinfunction "VSS_10") (pintype "power_in"))
      (node (ref "IC1") (pin "20") (pinfunction "VSSA_20") (pintype "power_in"))
      (node (ref "IC1") (pin "27") (pinfunction "VSS_4_27") (pintype "power_in"))
      (node (ref "IC1") (pin "44") (pinfunction "PE13_44") (pintype "bidirectional"))
      (node (ref "IC1") (pin "45") (pinfunction "PE14_45") (pintype "bidirectional"))
      (node (ref "IC1") (pin "46") (pinfunction "PE15_46") (pintype "bidirectional"))
      (node (ref "IC1") (pin "74") (pinfunction "VSS_74") (pintype "power_in"))
      (node (ref "IC1") (pin "99") (pinfunction "VSS_99") (pintype "power_in"))
      (node (ref "J1") (pin "4") (pinfunction "S_4") (pintype "passive"))
      (node (ref "J2") (pin "6") (pinfunction "S_6") (pintype "passive"))
      (node (ref "J3") (pin "6") (pinfunction "S_6") (pintype "passive"))
      (node (ref "J4") (pin "GND") (pinfunction "S_GND") (pintype "passive"))
      (node (ref "J5") (pin "GND") (pinfunction "5_GND") (pintype "power_in"))
      (node (ref "J5") (pin "GND1") (pinfunction "GND1_GND1") (pintype "bidirectional"))
      (node (ref "J5") (pin "GND2") (pinfunction "GND2_GND2") (pintype "bidirectional"))
      (node (ref "J5") (pin "GND3") (pinfunction "GND3_GND3") (pintype "bidirectional"))
      (node (ref "J5") (pin "GND4") (pinfunction "GND4_GND4") (pintype "bidirectional"))
      (node (ref "J6") (pin "3") (pinfunction "S_3") (pintype "passive"))
      (node (ref "J6") (pin "5") (pinfunction "S_5") (pintype "passive"))
      (node (ref "J6") (pin "9") (pinfunction "S_9") (pintype "passive"))
      (node (ref "Q1") (pin "3") (pinfunction "G_3") (pintype "passive"))
      (node (ref "R13") (pin "1") (pinfunction "1_1") (pintype "passive"))
      (node (ref "R18") (pin "1") (pinfunction "1_1") (pintype "passive"))
      (node (ref "R5") (pin "2") (pinfunction "2_2") (pintype "passive"))
      (node (ref "S1") (pin "B3") (pinfunction "2_B3") (pintype "passive"))
      (node (ref "U$5") (pin "11") (pinfunction "SER_DATAIN_P_11") (pintype "input"))
      (node (ref "U$5") (pin "12") (pinfunction "LVDS_GND_12") (pintype "power_in"))
      (node (ref "U$5") (pin "13") (pinfunction "DGND_13") (pintype "power_in"))
      (node (ref "U$5") (pin "29") (pinfunction "RSVD_29") (pintype "input"))
      (node (ref "U$5") (pin "34") (pinfunction "AGND_34") (pintype "power_in"))
      (node (ref "U$5") (pin "38") (pinfunction "AGND_38") (pintype "power_in"))
      (node (ref "U$5") (pin "48") (pinfunction "DGND_48") (pintype "power_in"))
      (node (ref "U$5") (pin "7") (pinfunction "LVDS_GND_7") (pintype "power_in"))
      (node (ref "U$5") (pin "9") (pinfunction "BYPASS_CLKIN_P_9") (pintype "input"))
      (node (ref "U1") (pin "2") (pinfunction "GND_2") (pintype "input"))
      (node (ref "U12") (pin "10") (pinfunction "RES_P10_GND_10") (pintype "bidirectional"))
      (node (ref "U12") (pin "11") (pinfunction "RES_P11_VDD_11") (pintype "bidirectional"))
      (node (ref "U12") (pin "12") (pinfunction "RES_P12_GND_12") (pintype "bidirectional"))
      (node (ref "U12") (pin "13") (pinfunction "GND_13") (pintype "bidirectional"))
      (node (ref "U12") (pin "8") (pinfunction "RES_P8_GND_8") (pintype "bidirectional"))
      (node (ref "U12") (pin "9") (pinfunction "RES_P9_GND_9") (pintype "bidirectional"))
      (node (ref "U8") (pin "1") (pinfunction "A0_1") (pintype "bidirectional"))
      (node (ref "U8") (pin "2") (pinfunction "A1_2") (pintype "bidirectional"))
      (node (ref "U8") (pin "3") (pinfunction "A2_3") (pintype "bidirectional"))
      (node (ref "U8") (pin "4") (pinfunction "VSS_4") (pintype "power_in"))
      (node (ref "X1") (pin "2") (pinfunction "NC_2_2") (pintype "power_in"))
      (node (ref "X1") (pin "4") (pinfunction "NC_4_4") (pintype "power_in"))
    )
    (net (code "29") (name "I2C1_SCL") (class "Default")
      (node (ref "IC1") (pin "95") (pinfunction "PB8_95") (pintype "bidirectional"))
      (node (ref "R3") (pin "1") (pinfunction "1_1") (pintype "passive"))
    )
    (net (code "30") (name "I2C1_SCL_EXT") (class "Default")
      (node (ref "J1") (pin "2") (pinfunction "S_2") (pintype "passive"))
      (node (ref "R3") (pin "2") (pinfunction "2_2") (pintype "passive"))
    )
    (net (code "31") (name "I2C1_SDA") (class "Default")
      (node (ref "IC1") (pin "96") (pinfunction "PB9_96") (pintype "bidirectional"))
      (node (ref "R4") (pin "1") (pinfunction "1_1") (pintype "passive"))
    )
    (net (code "32") (name "I2C1_SDA_EXT") (class "Default")
      (node (ref "J1") (pin "3") (pinfunction "S_3") (pintype "passive"))
      (node (ref "R4") (pin "2") (pinfunction "2_2") (pintype "passive"))
    )
    (net (code "33") (name "I2C2_SCL") (class "Default")
      (node (ref "IC1") (pin "47") (pinfunction "PB10_47") (pintype "bidirectional"))
      (node (ref "R1") (pin "P$1") (pinfunction "1_P$1") (pintype "passive"))
      (node (ref "U$5") (pin "25") (pinfunction "SCLK_25") (pintype "input"))
      (node (ref "U8") (pin "6") (pinfunction "SCL_6") (pintype "bidirectional"))
    )
    (net (code "34") (name "I2C2_SDA") (class "Default")
      (node (ref "IC1") (pin "48") (pinfunction "PB11_48") (pintype "bidirectional"))
      (node (ref "R2") (pin "P$1") (pinfunction "1_P$1") (pintype "passive"))
      (node (ref "U$5") (pin "24") (pinfunction "SDATA_24") (pintype "bidirectional"))
      (node (ref "U8") (pin "5") (pinfunction "SDA_5") (pintype "bidirectional"))
    )
    (net (code "35") (name "I2C3_SCL---") (class "Default")
      (node (ref "IC1") (pin "67") (pinfunction "PA8_67") (pintype "bidirectional"))
    )
    (net (code "36") (name "JTCK-SWCLK") (class "Default")
      (node (ref "IC1") (pin "76") (pinfunction "PA14_76") (pintype "bidirectional"))
      (node (ref "J6") (pin "4") (pinfunction "S_4") (pintype "passive"))
    )
    (net (code "37") (name "JTDI") (class "Default")
      (node (ref "IC1") (pin "77") (pinfunction "PA15_77") (pintype "bidirectional"))
      (node (ref "J6") (pin "8") (pinfunction "S_8") (pintype "passive"))
    )
    (net (code "38") (name "JTDO") (class "Default")
      (node (ref "IC1") (pin "89") (pinfunction "PB3_89") (pintype "bidirectional"))
      (node (ref "J6") (pin "6") (pinfunction "S_6") (pintype "passive"))
    )
    (net (code "39") (name "JTMS-SWDIO") (class "Default")
      (node (ref "IC1") (pin "72") (pinfunction "PA13_72") (pintype "bidirectional"))
      (node (ref "J6") (pin "2") (pinfunction "S_2") (pintype "passive"))
    )
    (net (code "40") (name "LED_AMBER") (class "Default")
      (node (ref "IC1") (pin "1") (pinfunction "PE2_1") (pintype "bidirectional"))
      (node (ref "R14") (pin "1") (pinfunction "1_1") (pintype "passive"))
    )
    (net (code "41") (name "LED_BLUE") (class "Default")
      (node (ref "IC1") (pin "2") (pinfunction "PE3_2") (pintype "bidirectional"))
      (node (ref "R15") (pin "1") (pinfunction "1_1") (pintype "passive"))
    )
    (net (code "42") (name "LED_RED") (class "Default")
      (node (ref "IC1") (pin "38") (pinfunction "PE7_38") (pintype "bidirectional"))
      (node (ref "R17") (pin "1") (pinfunction "1_1") (pintype "passive"))
    )
    (net (code "43") (name "MAG_DRDY---") (class "Default")
      (node (ref "IC1") (pin "36") (pinfunction "PB1_36") (pintype "bidirectional"))
    )
    (net (code "44") (name "Net-(C3-1)") (class "Default")
      (node (ref "C3") (pin "P$1") (pinfunction "1_P$1") (pintype "passive"))
      (node (ref "IC1") (pin "12") (pinfunction "OSC_IN_12") (pintype "input"))
      (node (ref "X1") (pin "3") (pinfunction "3_3") (pintype "bidirectional"))
    )
    (net (code "45") (name "Net-(C4-2)") (class "Default")
      (node (ref "C4") (pin "P$2") (pinfunction "2_P$2") (pintype "passive"))
      (node (ref "IC1") (pin "13") (pinfunction "OSC_OUT_13") (pintype "output"))
      (node (ref "X1") (pin "1") (pinfunction "1_1") (pintype "bidirectional"))
    )
    (net (code "46") (name "Net-(D1-A)") (class "Default")
      (node (ref "D1") (pin "ANODE") (pinfunction "A_ANODE") (pintype "passive"))
      (node (ref "L8") (pin "P$1") (pinfunction "1_P$1") (pintype "passive"))
    )
    (net (code "47") (name "Net-(IC1B-VCAP_1)") (class "Default")
      (node (ref "C11") (pin "1") (pinfunction "1_1") (pintype "passive"))
      (node (ref "IC1") (pin "49") (pinfunction "VCAP_1_49") (pintype "power_in"))
    )
    (net (code "48") (name "Net-(IC1B-VCAP_2)") (class "Default")
      (node (ref "C12") (pin "1") (pinfunction "1_1") (pintype "passive"))
      (node (ref "IC1") (pin "73") (pinfunction "VCAP_2_73") (pintype "power_in"))
    )
    (net (code "49") (name "Net-(IC1N-BOOT0)") (class "Default")
      (node (ref "BOOT0") (pin "P$1") (pinfunction "P$1_P$1") (pintype "passive"))
      (node (ref "IC1") (pin "94") (pinfunction "BOOT0_94") (pintype "input"))
      (node (ref "R18") (pin "2") (pinfunction "2_2") (pintype "passive"))
    )
    (net (code "50") (name "Net-(J1A-S)") (class "Default")
      (node (ref "J1") (pin "1") (pinfunction "S_1") (pintype "passive"))
      (node (ref "L2") (pin "P$2") (pinfunction "2_P$2") (pintype "passive"))
    )
    (net (code "51") (name "Net-(J2A-S)") (class "Default")
      (node (ref "J2") (pin "1") (pinfunction "S_1") (pintype "passive"))
      (node (ref "JP2") (pin "2") (pinfunction "2_2") (pintype "passive"))
    )
    (net (code "52") (name "Net-(J5-4)") (class "Default")
      (node (ref "J5") (pin "ID") (pinfunction "4_ID") (pintype "passive"))
      (node (ref "R7") (pin "1") (pinfunction "1_1") (pintype "passive"))
    )
    (net (code "53") (name "Net-(LED1-PadC)") (class "Default")
      (node (ref "LED1") (pin "C") (pinfunction "C_C") (pintype "passive"))
      (node (ref "R13") (pin "2") (pinfunction "2_2") (pintype "passive"))
    )
    (net (code "54") (name "Net-(LED2-PadC)") (class "Default")
      (node (ref "LED2") (pin "C") (pinfunction "C_C") (pintype "passive"))
      (node (ref "R14") (pin "2") (pinfunction "2_2") (pintype "passive"))
    )
    (net (code "55") (name "Net-(LED3-PadC)") (class "Default")
      (node (ref "LED3") (pin "C") (pinfunction "C_C") (pintype "passive"))
      (node (ref "R15") (pin "2") (pinfunction "2_2") (pintype "passive"))
    )
    (net (code "56") (name "Net-(LED4-PadC)") (class "Default")
      (node (ref "LED4") (pin "C") (pinfunction "C_C") (pintype "passive"))
      (node (ref "R17") (pin "2") (pinfunction "2_2") (pintype "passive"))
    )
    (net (code "57") (name "Net-(U$5-BYPASS_CLKIN_N)") (class "Default")
      (node (ref "R19") (pin "1") (pinfunction "1_1") (pintype "passive"))
      (node (ref "U$5") (pin "8") (pinfunction "BYPASS_CLKIN_N_8") (pintype "input"))
    )
    (net (code "58") (name "Net-(U$5-SER_DATAIN_N)") (class "Default")
      (node (ref "R20") (pin "1") (pinfunction "1_1") (pintype "passive"))
      (node (ref "U$5") (pin "10") (pinfunction "SER_DATAIN_N_10") (pintype "input"))
    )
    (net (code "59") (name "Net-(U1-BP)") (class "Default")
      (node (ref "C13") (pin "1") (pinfunction "1_1") (pintype "passive"))
      (node (ref "U1") (pin "4") (pinfunction "BP_4") (pintype "input"))
    )
    (net (code "60") (name "Net-(U12-PLLFILT)") (class "Default")
      (node (ref "C25") (pin "1") (pinfunction "1_1") (pintype "passive"))
      (node (ref "U12") (pin "14") (pinfunction "PLLFILT_14") (pintype "bidirectional"))
    )
    (net (code "61") (name "OTG_FS_ID") (class "Default")
      (node (ref "IC1") (pin "69") (pinfunction "PA10_69") (pintype "bidirectional"))
      (node (ref "R7") (pin "2") (pinfunction "2_2") (pintype "passive"))
    )
    (net (code "62") (name "OTG_FS_N") (class "Default")
      (node (ref "IC1") (pin "70") (pinfunction "PA11_70") (pintype "bidirectional"))
      (node (ref "R6") (pin "2") (pinfunction "2_2") (pintype "passive"))
    )
    (net (code "63") (name "OTG_FS_P") (class "Default")
      (node (ref "IC1") (pin "71") (pinfunction "PA12_71") (pintype "bidirectional"))
      (node (ref "R8") (pin "2") (pinfunction "2_2") (pintype "passive"))
    )
    (net (code "64") (name "OTG_N") (class "Default")
      (node (ref "J5") (pin "D-") (pinfunction "2_D-") (pintype "bidirectional"))
      (node (ref "OTG_DM") (pin "P$1") (pinfunction "P$1_P$1") (pintype "passive"))
      (node (ref "R6") (pin "1") (pinfunction "1_1") (pintype "passive"))
    )
    (net (code "65") (name "OTG_P") (class "Default")
      (node (ref "J5") (pin "D+") (pinfunction "3_D+") (pintype "bidirectional"))
      (node (ref "OTG_DP") (pin "P$1") (pinfunction "P$1_P$1") (pintype "passive"))
      (node (ref "R8") (pin "1") (pinfunction "1_1") (pintype "passive"))
    )
    (net (code "66") (name "PB2-BOOT1") (class "Default")
      (node (ref "BOOT1") (pin "P$1") (pinfunction "P$1_P$1") (pintype "passive"))
      (node (ref "IC1") (pin "37") (pinfunction "PB2_37") (pintype "bidirectional"))
      (node (ref "R5") (pin "1") (pinfunction "1_1") (pintype "passive"))
    )
    (net (code "67") (name "PRES_DRDY---") (class "Default")
      (node (ref "IC1") (pin "35") (pinfunction "PB0_35") (pintype "bidirectional"))
    )
    (net (code "68") (name "SONAR_TX") (class "Default")
      (node (ref "J4") (pin "TX") (pinfunction "S_TX") (pintype "passive"))
      (node (ref "R11") (pin "1") (pinfunction "1_1") (pintype "passive"))
    )
    (net (code "69") (name "SPI1_MOSI---") (class "Default")
      (node (ref "IC1") (pin "32") (pinfunction "PA7_32") (pintype "bidirectional"))
    )
    (net (code "70") (name "SPI2_MISO") (class "Default")
      (node (ref "IC1") (pin "53") (pinfunction "PB14_53") (pintype "bidirectional"))
      (node (ref "U12") (pin "4") (pinfunction "SDO/SA0_4") (pintype "bidirectional"))
    )
    (net (code "71") (name "SPI2_MOSI") (class "Default")
      (node (ref "IC1") (pin "54") (pinfunction "PB15_54") (pintype "bidirectional"))
      (node (ref "U12") (pin "3") (pinfunction "SDA/SDI/SDO_3") (pintype "bidirectional"))
    )
    (net (code "72") (name "SPI2_NSS") (class "Default")
      (node (ref "IC1") (pin "51") (pinfunction "PB12_51") (pintype "bidirectional"))
      (node (ref "U12") (pin "5") (pinfunction "CS_5") (pintype "input"))
    )
    (net (code "73") (name "SPI2_SCK") (class "Default")
      (node (ref "IC1") (pin "52") (pinfunction "PB13_52") (pintype "bidirectional"))
      (node (ref "U12") (pin "2") (pinfunction "SCL/SPC_2") (pintype "input"))
    )
    (net (code "74") (name "TIM1_CH1") (class "Default")
      (node (ref "IC1") (pin "40") (pinfunction "PE9_40") (pintype "bidirectional"))
    )
    (net (code "75") (name "TIM1_CH2") (class "Default")
      (node (ref "IC1") (pin "42") (pinfunction "PE11_42") (pintype "bidirectional"))
    )
    (net (code "76") (name "TIM4_CH2") (class "Default")
      (node (ref "IC1") (pin "60") (pinfunction "PD13_60") (pintype "bidirectional"))
      (node (ref "J4") (pin "PW") (pinfunction "S_PW") (pintype "passive"))
    )
    (net (code "77") (name "TIM4_CH3") (class "Default")
      (node (ref "IC1") (pin "61") (pinfunction "PD14_61") (pintype "bidirectional"))
    )
    (net (code "78") (name "TIM4_CH4") (class "Default")
      (node (ref "IC1") (pin "62") (pinfunction "PD15_62") (pintype "bidirectional"))
    )
    (net (code "79") (name "TIM5_CH1") (class "Default")
      (node (ref "IC1") (pin "23") (pinfunction "PA0_23") (pintype "bidirectional"))
    )
    (net (code "80") (name "TIM5_CH2") (class "Default")
      (node (ref "IC1") (pin "24") (pinfunction "PA1_24") (pintype "bidirectional"))
    )
    (net (code "81") (name "TIM5_CH3_EXPOSURE") (class "Default")
      (node (ref "IC1") (pin "25") (pinfunction "PA2_25") (pintype "bidirectional"))
      (node (ref "U$5") (pin "23") (pinfunction "EXPOSURE_23") (pintype "input"))
    )
    (net (code "82") (name "TIM5_CH4_STANDBY") (class "Default")
      (node (ref "IC1") (pin "26") (pinfunction "PA3_26") (pintype "bidirectional"))
      (node (ref "U$5") (pin "33") (pinfunction "STANDBY_33") (pintype "input"))
    )
    (net (code "83") (name "TIM8_CH3_MASTERCLOCK") (class "Default")
      (node (ref "IC1") (pin "65") (pinfunction "PC8_65") (pintype "bidirectional"))
      (node (ref "U$5") (pin "47") (pinfunction "SYSCLK_47") (pintype "input"))
    )
    (net (code "84") (name "TIM8_CH4_LED_OUT") (class "Default")
      (node (ref "IC1") (pin "66") (pinfunction "PC9_66") (pintype "bidirectional"))
      (node (ref "U$5") (pin "27") (pinfunction "LED_OUT_27") (pintype "output"))
    )
    (net (code "85") (name "UART4_RX") (class "Default")
      (node (ref "IC1") (pin "79") (pinfunction "PC11_79") (pintype "bidirectional"))
      (node (ref "R10") (pin "2") (pinfunction "2_2") (pintype "passive"))
      (node (ref "R11") (pin "2") (pinfunction "2_2") (pintype "passive"))
    )
    (net (code "86") (name "USART2_CK") (class "Default")
      (node (ref "IC1") (pin "88") (pinfunction "PD7_88") (pintype "bidirectional"))
    )
    (net (code "87") (name "USART2_CTS") (class "Default")
      (node (ref "IC1") (pin "84") (pinfunction "PD3_84") (pintype "bidirectional"))
      (node (ref "J2") (pin "4") (pinfunction "S_4") (pintype "passive"))
    )
    (net (code "88") (name "USART2_RTS") (class "Default")
      (node (ref "IC1") (pin "85") (pinfunction "PD4_85") (pintype "bidirectional"))
      (node (ref "J2") (pin "5") (pinfunction "S_5") (pintype "passive"))
    )
    (net (code "89") (name "USART2_RX") (class "Default")
      (node (ref "IC1") (pin "87") (pinfunction "PD6_87") (pintype "bidirectional"))
      (node (ref "J2") (pin "3") (pinfunction "S_3") (pintype "passive"))
      (node (ref "USART2_RX") (pin "P$1") (pinfunction "P$1_P$1") (pintype "passive"))
    )
    (net (code "90") (name "USART2_TX") (class "Default")
      (node (ref "IC1") (pin "86") (pinfunction "PD5_86") (pintype "bidirectional"))
      (node (ref "J2") (pin "2") (pinfunction "S_2") (pintype "passive"))
      (node (ref "USART2_TX") (pin "P$1") (pinfunction "P$1_P$1") (pintype "passive"))
    )
    (net (code "91") (name "USART3_CK") (class "Default")
      (node (ref "IC1") (pin "57") (pinfunction "PD10_57") (pintype "bidirectional"))
    )
    (net (code "92") (name "USART3_CTS") (class "Default")
      (node (ref "IC1") (pin "58") (pinfunction "PD11_58") (pintype "bidirectional"))
      (node (ref "J3") (pin "5") (pinfunction "S_5") (pintype "passive"))
    )
    (net (code "93") (name "USART3_RTS") (class "Default")
      (node (ref "IC1") (pin "59") (pinfunction "PD12_59") (pintype "bidirectional"))
      (node (ref "J3") (pin "4") (pinfunction "S_4") (pintype "passive"))
    )
    (net (code "94") (name "USART3_RX") (class "Default")
      (node (ref "IC1") (pin "56") (pinfunction "PD9_56") (pintype "bidirectional"))
      (node (ref "J3") (pin "2") (pinfunction "S_2") (pintype "passive"))
      (node (ref "USART3_RX") (pin "P$1") (pinfunction "P$1_P$1") (pintype "passive"))
    )
    (net (code "95") (name "USART3_TX") (class "Default")
      (node (ref "IC1") (pin "55") (pinfunction "PD8_55") (pintype "bidirectional"))
      (node (ref "J3") (pin "3") (pinfunction "S_3") (pintype "passive"))
      (node (ref "USART3_TX") (pin "P$1") (pinfunction "P$1_P$1") (pintype "passive"))
    )
    (net (code "96") (name "US_EN1") (class "Default")
      (node (ref "IC1") (pin "39") (pinfunction "PE8_39") (pintype "bidirectional"))
      (node (ref "J4") (pin "RX") (pinfunction "S_RX") (pintype "passive"))
    )
    (net (code "97") (name "US_EN2") (class "Default")
      (node (ref "IC1") (pin "41") (pinfunction "PE10_41") (pintype "bidirectional"))
    )
    (net (code "98") (name "VBUS") (class "Default")
      (node (ref "IC1") (pin "68") (pinfunction "PA9_68") (pintype "bidirectional"))
      (node (ref "J5") (pin "VBUS") (pinfunction "1_VBUS") (pintype "power_in"))
      (node (ref "L8") (pin "P$2") (pinfunction "2_P$2") (pintype "passive"))
      (node (ref "USB_VBUS") (pin "P$1") (pinfunction "P$1_P$1") (pintype "passive"))
    )
    (net (code "99") (name "VDD_3V3") (class "Default")
      (node (ref "C10") (pin "1") (pinfunction "1_1") (pintype "passive"))
      (node (ref "C16") (pin "1") (pinfunction "1_1") (pintype "passive"))
      (node (ref "C18") (pin "1") (pinfunction "1_1") (pintype "passive"))
      (node (ref "C2") (pin "1") (pinfunction "1_1") (pintype "passive"))
      (node (ref "C28") (pin "1") (pinfunction "1_1") (pintype "passive"))
      (node (ref "C29") (pin "1") (pinfunction "1_1") (pintype "passive"))
      (node (ref "C30") (pin "1") (pinfunction "1_1") (pintype "passive"))
      (node (ref "C31") (pin "1") (pinfunction "1_1") (pintype "passive"))
      (node (ref "C32") (pin "1") (pinfunction "1_1") (pintype "passive"))
      (node (ref "C5") (pin "1") (pinfunction "1_1") (pintype "passive"))
      (node (ref "C6") (pin "A") (pinfunction "+_A") (pintype "passive"))
      (node (ref "C8") (pin "1") (pinfunction "1_1") (pintype "passive"))
      (node (ref "C9") (pin "1") (pinfunction "1_1") (pintype "passive"))
      (node (ref "IC1") (pin "100") (pinfunction "VDD_100") (pintype "power_in"))
      (node (ref "IC1") (pin "11") (pinfunction "VDD_11") (pintype "power_in"))
      (node (ref "IC1") (pin "19") (pinfunction "VDD_19") (pintype "power_in"))
      (node (ref "IC1") (pin "28") (pinfunction "VDD_28") (pintype "power_in"))
      (node (ref "IC1") (pin "43") (pinfunction "PE12_43") (pintype "bidirectional"))
      (node (ref "IC1") (pin "50") (pinfunction "VDD_50") (pintype "power_in"))
      (node (ref "IC1") (pin "6") (pinfunction "VBAT_6") (pintype "power_in"))
      (node (ref "IC1") (pin "75") (pinfunction "VDD_75") (pintype "power_in"))
      (node (ref "J6") (pin "1") (pinfunction "S_1") (pintype "passive"))
      (node (ref "JP1") (pin "3") (pinfunction "3_3") (pintype "passive"))
      (node (ref "L11") (pin "P$1") (pinfunction "1_P$1") (pintype "passive"))
      (node (ref "LED1") (pin "A") (pinfunction "A_A") (pintype "passive"))
      (node (ref "LED2") (pin "A") (pinfunction "A_A") (pintype "passive"))
      (node (ref "LED3") (pin "A") (pinfunction "A_A") (pintype "passive"))
      (node (ref "LED4") (pin "A") (pinfunction "A_A") (pintype "passive"))
      (node (ref "R1") (pin "P$2") (pinfunction "2_P$2") (pintype "passive"))
      (node (ref "R16") (pin "2") (pinfunction "2_2") (pintype "passive"))
      (node (ref "R19") (pin "2") (pinfunction "2_2") (pintype "passive"))
      (node (ref "R2") (pin "P$2") (pinfunction "2_P$2") (pintype "passive"))
      (node (ref "R20") (pin "2") (pinfunction "2_2") (pintype "passive"))
      (node (ref "R9") (pin "2") (pinfunction "2_2") (pintype "passive"))
      (node (ref "U$5") (pin "1") (pinfunction "VDD_1") (pintype "input"))
      (node (ref "U$5") (pin "14") (pinfunction "VDD_14") (pintype "input"))
      (node (ref "U$5") (pin "28") (pinfunction "OE_28") (pintype "input"))
      (node (ref "U$5") (pin "30") (pinfunction "SCTRL_ADR0_30") (pintype "input"))
      (node (ref "U$5") (pin "31") (pinfunction "SCTRL_ADR1_31") (pintype "input"))
      (node (ref "U$5") (pin "6") (pinfunction "VDD_LVDS_6") (pintype "input"))
      (node (ref "U1") (pin "5") (pinfunction "OUT_5") (pintype "passive"))
      (node (ref "U12") (pin "1") (pinfunction "VDD_IO_1") (pintype "bidirectional"))
      (node (ref "U8") (pin "8") (pinfunction "VCC_8") (pintype "power_in"))
      (node (ref "VDD_3V3") (pin "P$1") (pinfunction "P$1_P$1") (pintype "passive"))
    )
    (net (code "100") (name "VDD_3V3_ANALOG") (class "Default")
      (node (ref "C15") (pin "1") (pinfunction "1_1") (pintype "passive"))
      (node (ref "C19") (pin "1") (pinfunction "1_1") (pintype "passive"))
      (node (ref "C20") (pin "1") (pinfunction "1_1") (pintype "passive"))
      (node (ref "C21") (pin "1") (pinfunction "1_1") (pintype "passive"))
      (node (ref "C22") (pin "1") (pinfunction "1_1") (pintype "passive"))
      (node (ref "C23") (pin "1") (pinfunction "1_1") (pintype "passive"))
      (node (ref "C24") (pin "1") (pinfunction "1_1") (pintype "passive"))
      (node (ref "C26") (pin "1") (pinfunction "1_1") (pintype "passive"))
      (node (ref "IC1") (pin "21") (pinfunction "VREF+_21") (pintype "input"))
      (node (ref "IC1") (pin "22") (pinfunction "VDDA_22") (pintype "power_in"))
      (node (ref "L11") (pin "P$2") (pinfunction "2_P$2") (pintype "passive"))
      (node (ref "U$5") (pin "35") (pinfunction "VAA_35") (pintype "input"))
      (node (ref "U$5") (pin "39") (pinfunction "VAA_39") (pintype "input"))
      (node (ref "U$5") (pin "40") (pinfunction "VAA_PIX_40") (pintype "input"))
      (node (ref "U12") (pin "15") (pinfunction "RES_P15_VDD_15") (pintype "bidirectional"))
      (node (ref "U12") (pin "16") (pinfunction "VDD_16") (pintype "bidirectional"))
      (node (ref "VDD_3V3_ANALOG") (pin "P$1") (pinfunction "P$1_P$1") (pintype "passive"))
    )
    (net (code "101") (name "VDD_5V") (class "Default")
      (node (ref "C27") (pin "A") (pinfunction "+_A") (pintype "passive"))
      (node (ref "C7") (pin "1") (pinfunction "1_1") (pintype "passive"))
      (node (ref "D1") (pin "CATHODE") (pinfunction "C_CATHODE") (pintype "passive"))
      (node (ref "JP1") (pin "1") (pinfunction "1_1") (pintype "passive"))
      (node (ref "JP2") (pin "1") (pinfunction "1_1") (pintype "passive"))
      (node (ref "Q1") (pin "4") (pinfunction "S_4") (pintype "passive"))
      (node (ref "R10") (pin "1") (pinfunction "1_1") (pintype "passive"))
      (node (ref "U1") (pin "1") (pinfunction "IN_1") (pintype "input"))
      (node (ref "U1") (pin "3") (pinfunction "EN_3") (pintype "input"))
      (node (ref "VDD_5V") (pin "P$1") (pinfunction "P$1_P$1") (pintype "passive"))
    )
    (net (code "102") (name "VDD_5V_IN") (class "Default")
      (node (ref "L1") (pin "P$1") (pinfunction "1_P$1") (pintype "passive"))
      (node (ref "L2") (pin "P$1") (pinfunction "1_P$1") (pintype "passive"))
      (node (ref "Q1") (pin "1") (pinfunction "D_1") (pintype "passive"))
      (node (ref "Q1") (pin "2") (pinfunction "D1_2") (pintype "passive"))
      (node (ref "Q1") (pin "5") (pinfunction "D2_5") (pintype "passive"))
      (node (ref "Q1") (pin "6") (pinfunction "D3_6") (pintype "passive"))
    )
    (net (code "103") (name "VDD_5V_IN_UART3") (class "Default")
      (node (ref "J3") (pin "1") (pinfunction "S_1") (pintype "passive"))
      (node (ref "L1") (pin "P$2") (pinfunction "2_P$2") (pintype "passive"))
      (node (ref "VDD_5V_IN") (pin "P$1") (pinfunction "P$1_P$1") (pintype "passive"))
    )
    (net (code "104") (name "VDD_SONAR") (class "Default")
      (node (ref "J4") (pin "VDD") (pinfunction "S_VDD") (pintype "passive"))
      (node (ref "JP1") (pin "2") (pinfunction "2_2") (pintype "passive"))
    )
    (net (code "105") (name "unconnected-(J4B-S-PadBW)") (class "Default")
      (node (ref "J4") (pin "BW") (pinfunction "S_BW") (pintype "passive"))
    )
    (net (code "106") (name "unconnected-(U$5-NC-Pad36)") (class "Default")
      (node (ref "U$5") (pin "36") (pinfunction "NC_36") (pintype "no_connect"))
    )
    (net (code "107") (name "unconnected-(U$5-NC-Pad37)") (class "Default")
      (node (ref "U$5") (pin "37") (pinfunction "NC_37") (pintype "no_connect"))
    )
    (net (code "108") (name "unconnected-(U$5-SER_DATAOUT_N-Pad4)") (class "Default")
      (node (ref "U$5") (pin "4") (pinfunction "SER_DATAOUT_N_4") (pintype "output"))
    )
    (net (code "109") (name "unconnected-(U$5-SER_DATAOUT_P-Pad5)") (class "Default")
      (node (ref "U$5") (pin "5") (pinfunction "SER_DATAOUT_P_5") (pintype "output"))
    )
    (net (code "110") (name "unconnected-(U$5-SHFT_CLKOUT_N-Pad2)") (class "Default")
      (node (ref "U$5") (pin "2") (pinfunction "SHFT_CLKOUT_N_2") (pintype "output"))
    )
    (net (code "111") (name "unconnected-(U$5-SHFT_CLKOUT_P-Pad3)") (class "Default")
      (node (ref "U$5") (pin "3") (pinfunction "SHFT_CLKOUT_P_3") (pintype "output"))
    )
    (net (code "112") (name "unconnected-(U$5-STFRM_OUT-Pad26)") (class "Default")
      (node (ref "U$5") (pin "26") (pinfunction "STFRM_OUT_26") (pintype "bidirectional"))
    )
    (net (code "113") (name "unconnected-(U$5-STLN_OUT-Pad22)") (class "Default")
      (node (ref "U$5") (pin "22") (pinfunction "STLN_OUT_22") (pintype "bidirectional"))
    )
    (net (code "114") (name "unconnected-(U8-WP-Pad7)") (class "Default")
      (node (ref "U8") (pin "7") (pinfunction "WP_7") (pintype "bidirectional"))
    )
    (net (code "115") (name "unconnected-(U12-DRDY{slash}INT2-Pad6)") (class "Default")
      (node (ref "U12") (pin "6") (pinfunction "DRDY/INT2_6") (pintype "output"))
    )
    (net (code "116") (name "unconnected-(U12-INT1-Pad7)") (class "Default")
      (node (ref "U12") (pin "7") (pinfunction "INT1_7") (pintype "output"))
    )
    (net (code "117") (name "~{JTRST}") (class "Default")
      (node (ref "IC1") (pin "90") (pinfunction "PB4_90") (pintype "bidirectional"))
      (node (ref "J6") (pin "10") (pinfunction "S_10") (pintype "passive"))
    )
    (net (code "118") (name "~{RESET}") (class "Default")
      (node (ref "!RESET") (pin "P$1") (pinfunction "P$1_P$1") (pintype "passive"))
      (node (ref "C17") (pin "2") (pinfunction "2_2") (pintype "passive"))
      (node (ref "IC1") (pin "14") (pinfunction "NRST_14") (pintype "input"))
      (node (ref "R16") (pin "1") (pinfunction "1_1") (pintype "passive"))
      (node (ref "S1") (pin "A1") (pinfunction "1_A1") (pintype "passive"))
    )
  )
)
